# di2c.net
KiCad netlist of a schematic drawn in Altium Designer
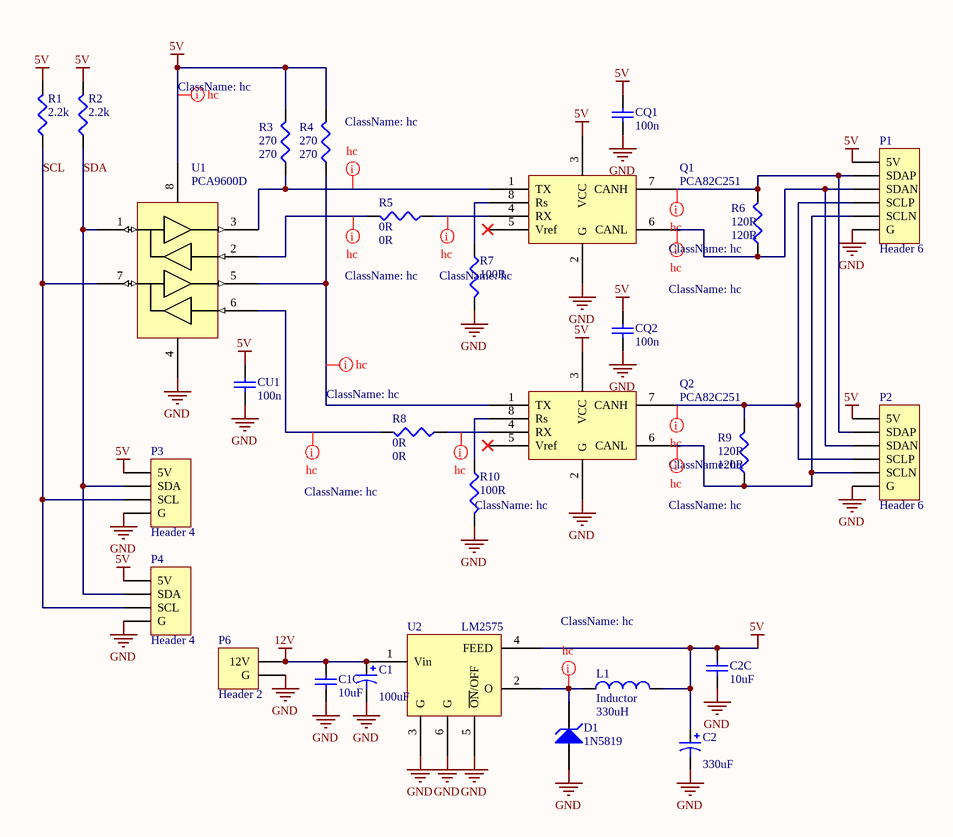
[diagram p0: di2c.SchDoc]

(export (version "E")
  (design (tool "Eeschema 10.0.6"))
  (components
    (comp (ref "C1")
      (value "100uF")
      (footprint "C7343")
      (description "Polarized Capacitor (Radial)")
      (fields (field (name "Comment") "Cap Pol1") (field (name "PUBLISHER") "Altium Limited"))
      (libsource (lib "Miscellaneous Devices") (part "Cap Pol1"))
    )
    (comp (ref "C1C")
      (value "10uF")
      (footprint "C1812")
      (description "Capacitor (Semiconductor SIM Model)")
      (fields (field (name "Comment") "Cap Semi") (field (name "PUBLISHER") "Altium Limited"))
      (libsource (lib "Miscellaneous Devices") (part "Cap Semi"))
    )
    (comp (ref "C2")
      (value "330uF")
      (footprint "C7343")
      (description "Polarized Capacitor (Radial)")
      (fields (field (name "Comment") "Cap Pol1") (field (name "PUBLISHER") "Altium Limited"))
      (libsource (lib "Miscellaneous Devices") (part "Cap Pol1"))
    )
    (comp (ref "C2C")
      (value "10uF")
      (footprint "C1812")
      (description "Capacitor (Semiconductor SIM Model)")
      (fields (field (name "Comment") "Cap Semi") (field (name "PUBLISHER") "Altium Limited"))
      (libsource (lib "Miscellaneous Devices") (part "Cap Semi"))
    )
    (comp (ref "CQ1")
      (value "100n")
      (footprint "C1206")
      (description "Capacitor (Semiconductor SIM Model)")
      (fields (field (name "Comment") "Cap Semi") (field (name "PUBLISHER") "Altium Limited"))
      (libsource (lib "Miscellaneous Devices") (part "Cap Semi"))
    )
    (comp (ref "CQ2")
      (value "100n")
      (footprint "C1206")
      (description "Capacitor (Semiconductor SIM Model)")
      (fields (field (name "Comment") "Cap Semi") (field (name "PUBLISHER") "Altium Limited"))
      (libsource (lib "Miscellaneous Devices") (part "Cap Semi"))
    )
    (comp (ref "CU1")
      (value "100n")
      (footprint "C1206")
      (description "Capacitor (Semiconductor SIM Model)")
      (fields (field (name "Comment") "Cap Semi") (field (name "PUBLISHER") "Altium Limited"))
      (libsource (lib "Miscellaneous Devices") (part "Cap Semi"))
    )
    (comp (ref "D1")
      (value "1N5819")
      (footprint "DO214AC")
      (description "Zener Diode")
      (fields (field (name "PUBLISHER") "Altium Limited"))
      (libsource (lib "Miscellaneous Devices") (part "D Zener"))
    )
    (comp (ref "L1")
      (value "Inductor")
      (footprint "CD74R")
      (fields (field (name "ALTIUM_VALUE") "330uH") (field (name "PUBLISHER") "Altium Limited"))
      (libsource (lib "Miscellaneous Devices") (part "Inductor"))
    )
    (comp (ref "P1")
      (value "Header 6")
      (footprint "HDR1X6")
      (description "Header, 6-Pin")
      (fields (field (name "PUBLISHER") "Altium Limited"))
      (libsource (lib "Miscellaneous Connectors") (part "Header 6"))
    )
    (comp (ref "P2")
      (value "Header 6")
      (footprint "HDR1X6")
      (description "Header, 6-Pin")
      (fields (field (name "PUBLISHER") "Altium Limited"))
      (libsource (lib "Miscellaneous Connectors") (part "Header 6"))
    )
    (comp (ref "P3")
      (value "Header 4")
      (footprint "HDR1X4")
      (description "Header, 4-Pin")
      (fields (field (name "PUBLISHER") "Altium Limited"))
      (libsource (lib "Miscellaneous Connectors") (part "Header 4"))
    )
    (comp (ref "P4")
      (value "Header 4")
      (footprint "HDR1X4")
      (description "Header, 4-Pin")
      (fields (field (name "PUBLISHER") "Altium Limited"))
      (libsource (lib "Miscellaneous Connectors") (part "Header 4"))
    )
    (comp (ref "P6")
      (value "Header 2")
      (footprint "HDR1X2")
      (description "Header, 2-Pin")
      (fields (field (name "PUBLISHER") "Altium Limited"))
      (libsource (lib "Miscellaneous Connectors") (part "Header 2"))
    )
    (comp (ref "Q1") (value "PCA82C251") (footprint "SOIC150-8_M") (libsource (lib "PCA") (part "PCA82C251")))
    (comp (ref "Q2") (value "PCA82C251") (footprint "SOIC150-8_M") (libsource (lib "PCA") (part "PCA82C251")))
    (comp (ref "R1")
      (value "2.2k")
      (footprint "J1-0603")
      (description "Resistor")
      (fields (field (name "PUBLISHER") "Altium Limited"))
      (libsource (lib "Miscellaneous Devices") (part "Res3"))
    )
    (comp (ref "R2")
      (value "2.2k")
      (footprint "J1-0603")
      (description "Resistor")
      (fields (field (name "PUBLISHER") "Altium Limited"))
      (libsource (lib "Miscellaneous Devices") (part "Res3"))
    )
    (comp (ref "R3")
      (value "270")
      (footprint "R1206")
      (description "Resistor")
      (fields (field (name "ALTIUM_VALUE") "270") (field (name "PUBLISHER") "Altium Limited"))
      (libsource (lib "Miscellaneous Devices") (part "Res3"))
    )
    (comp (ref "R4")
      (value "270")
      (footprint "R1206")
      (description "Resistor")
      (fields (field (name "ALTIUM_VALUE") "270") (field (name "PUBLISHER") "Altium Limited"))
      (libsource (lib "Miscellaneous Devices") (part "Res3"))
    )
    (comp (ref "R5")
      (value "0R")
      (footprint "R1206")
      (description "Resistor")
      (fields (field (name "ALTIUM_VALUE") "0R") (field (name "PUBLISHER") "Altium Limited"))
      (libsource (lib "Miscellaneous Devices") (part "Res3"))
    )
    (comp (ref "R6")
      (value "120R")
      (footprint "R1206")
      (description "Resistor")
      (fields (field (name "ALTIUM_VALUE") "120R") (field (name "PUBLISHER") "Altium Limited"))
      (libsource (lib "Miscellaneous Devices") (part "Res3"))
    )
    (comp (ref "R7")
      (value "100R")
      (footprint "J1-0603")
      (description "Resistor")
      (fields (field (name "PUBLISHER") "Altium Limited"))
      (libsource (lib "Miscellaneous Devices") (part "Res3"))
    )
    (comp (ref "R8")
      (value "0R")
      (footprint "R1206")
      (description "Resistor")
      (fields (field (name "ALTIUM_VALUE") "0R") (field (name "PUBLISHER") "Altium Limited"))
      (libsource (lib "Miscellaneous Devices") (part "Res3"))
    )
    (comp (ref "R9")
      (value "120R")
      (footprint "R1206")
      (description "Resistor")
      (fields (field (name "ALTIUM_VALUE") "120R") (field (name "PUBLISHER") "Altium Limited"))
      (libsource (lib "Miscellaneous Devices") (part "Res3"))
    )
    (comp (ref "R10")
      (value "100R")
      (footprint "J1-0603")
      (description "Resistor")
      (fields (field (name "PUBLISHER") "Altium Limited"))
      (libsource (lib "Miscellaneous Devices") (part "Res3"))
    )
    (comp (ref "U1") (value "PCA9600D") (footprint "SOIC150-8_M") (libsource (lib "misc") (part "P82B96")))
    (comp (ref "U2") (value "LM2575") (footprint "KTT") (libsource (lib "PCA") (part "LM2575")))
  )
  (nets
    (net (code "1") (name "/SCL") (class "Default")
      (node (ref "P3") (pin "2") (pinfunction "SCL_2") (pintype "passive"))
      (node (ref "P4") (pin "2") (pinfunction "SCL_2") (pintype "passive"))
      (node (ref "R1") (pin "1") (pinfunction "1_1") (pintype "passive"))
      (node (ref "U1") (pin "7") (pinfunction "7_7") (pintype "bidirectional"))
    )
    (net (code "2") (name "/SDA") (class "Default")
      (node (ref "P3") (pin "3") (pinfunction "SDA_3") (pintype "passive"))
      (node (ref "P4") (pin "3") (pinfunction "SDA_3") (pintype "passive"))
      (node (ref "R2") (pin "1") (pinfunction "1_1") (pintype "passive"))
      (node (ref "U1") (pin "1") (pinfunction "1_1") (pintype "bidirectional"))
    )
    (net (code "3") (name "5V") (class "Default")
      (node (ref "C2") (pin "1") (pinfunction "1_1") (pintype "passive"))
      (node (ref "C2C") (pin "2") (pinfunction "2_2") (pintype "passive"))
      (node (ref "CQ1") (pin "2") (pinfunction "2_2") (pintype "passive"))
      (node (ref "CQ2") (pin "2") (pinfunction "2_2") (pintype "passive"))
      (node (ref "CU1") (pin "2") (pinfunction "2_2") (pintype "passive"))
      (node (ref "L1") (pin "2") (pinfunction "2_2") (pintype "passive"))
      (node (ref "P1") (pin "6") (pinfunction "5V_6") (pintype "passive"))
      (node (ref "P2") (pin "6") (pinfunction "5V_6") (pintype "passive"))
      (node (ref "P3") (pin "4") (pinfunction "5V_4") (pintype "passive"))
      (node (ref "P4") (pin "4") (pinfunction "5V_4") (pintype "passive"))
      (node (ref "Q1") (pin "3") (pinfunction "VCC_3") (pintype "passive"))
      (node (ref "Q2") (pin "3") (pinfunction "VCC_3") (pintype "passive"))
      (node (ref "R1") (pin "2") (pinfunction "2_2") (pintype "passive"))
      (node (ref "R2") (pin "2") (pinfunction "2_2") (pintype "passive"))
      (node (ref "R3") (pin "2") (pinfunction "2_2") (pintype "passive"))
      (node (ref "R4") (pin "2") (pinfunction "2_2") (pintype "passive"))
      (node (ref "U1") (pin "8") (pinfunction "8_8") (pintype "passive"))
      (node (ref "U2") (pin "4") (pinfunction "FEED_4") (pintype "passive"))
    )
    (net (code "4") (name "12V") (class "Default")
      (node (ref "C1") (pin "1") (pinfunction "1_1") (pintype "passive"))
      (node (ref "C1C") (pin "2") (pinfunction "2_2") (pintype "passive"))
      (node (ref "P6") (pin "2") (pinfunction "12V_2") (pintype "passive"))
      (node (ref "U2") (pin "1") (pinfunction "Vin_1") (pintype "passive"))
    )
    (net (code "5") (name "GND") (class "Default")
      (node (ref "C1") (pin "2") (pinfunction "2_2") (pintype "passive"))
      (node (ref "C1C") (pin "1") (pinfunction "1_1") (pintype "passive"))
      (node (ref "C2") (pin "2") (pinfunction "2_2") (pintype "passive"))
      (node (ref "C2C") (pin "1") (pinfunction "1_1") (pintype "passive"))
      (node (ref "CQ1") (pin "1") (pinfunction "1_1") (pintype "passive"))
      (node (ref "CQ2") (pin "1") (pinfunction "1_1") (pintype "passive"))
      (node (ref "CU1") (pin "1") (pinfunction "1_1") (pintype "passive"))
      (node (ref "D1") (pin "2") (pinfunction "A_2") (pintype "passive"))
      (node (ref "P1") (pin "1") (pinfunction "G_1") (pintype "passive"))
      (node (ref "P2") (pin "1") (pinfunction "G_1") (pintype "passive"))
      (node (ref "P3") (pin "1") (pinfunction "G_1") (pintype "passive"))
      (node (ref "P4") (pin "1") (pinfunction "G_1") (pintype "passive"))
      (node (ref "P6") (pin "1") (pinfunction "G_1") (pintype "passive"))
      (node (ref "Q1") (pin "2") (pinfunction "G_2") (pintype "passive"))
      (node (ref "Q2") (pin "2") (pinfunction "G_2") (pintype "passive"))
      (node (ref "R10") (pin "2") (pinfunction "2_2") (pintype "passive"))
      (node (ref "R7") (pin "2") (pinfunction "2_2") (pintype "passive"))
      (node (ref "U1") (pin "4") (pinfunction "4_4") (pintype "passive"))
      (node (ref "U2") (pin "3") (pinfunction "G_3") (pintype "passive"))
      (node (ref "U2") (pin "5") (pinfunction "~{ON}/OFF_5") (pintype "passive"))
      (node (ref "U2") (pin "6") (pinfunction "G_6") (pintype "passive"))
    )
    (net (code "6") (name "Net-(D1-K)") (class "Default")
      (node (ref "D1") (pin "1") (pinfunction "K_1") (pintype "passive"))
      (node (ref "L1") (pin "1") (pinfunction "1_1") (pintype "passive"))
      (node (ref "U2") (pin "2") (pinfunction "O_2") (pintype "passive"))
    )
    (net (code "7") (name "Net-(P1-SCLN)") (class "Default")
      (node (ref "P1") (pin "2") (pinfunction "SCLN_2") (pintype "passive"))
      (node (ref "P2") (pin "2") (pinfunction "SCLN_2") (pintype "passive"))
      (node (ref "Q2") (pin "6") (pinfunction "CANL_6") (pintype "passive"))
      (node (ref "R9") (pin "1") (pinfunction "1_1") (pintype "passive"))
    )
    (net (code "8") (name "Net-(P1-SCLP)") (class "Default")
      (node (ref "P1") (pin "3") (pinfunction "SCLP_3") (pintype "passive"))
      (node (ref "P2") (pin "3") (pinfunction "SCLP_3") (pintype "passive"))
      (node (ref "Q2") (pin "7") (pinfunction "CANH_7") (pintype "passive"))
      (node (ref "R9") (pin "2") (pinfunction "2_2") (pintype "passive"))
    )
    (net (code "9") (name "Net-(P1-SDAN)") (class "Default")
      (node (ref "P1") (pin "4") (pinfunction "SDAN_4") (pintype "passive"))
      (node (ref "P2") (pin "4") (pinfunction "SDAN_4") (pintype "passive"))
      (node (ref "Q1") (pin "6") (pinfunction "CANL_6") (pintype "passive"))
      (node (ref "R6") (pin "1") (pinfunction "1_1") (pintype "passive"))
    )
    (net (code "10") (name "Net-(P1-SDAP)") (class "Default")
      (node (ref "P1") (pin "5") (pinfunction "SDAP_5") (pintype "passive"))
      (node (ref "P2") (pin "5") (pinfunction "SDAP_5") (pintype "passive"))
      (node (ref "Q1") (pin "7") (pinfunction "CANH_7") (pintype "passive"))
      (node (ref "R6") (pin "2") (pinfunction "2_2") (pintype "passive"))
    )
    (net (code "11") (name "Net-(Q1-RX)") (class "Default")
      (node (ref "Q1") (pin "4") (pinfunction "RX_4") (pintype "passive"))
      (node (ref "R5") (pin "1") (pinfunction "1_1") (pintype "passive"))
    )
    (net (code "12") (name "Net-(Q1-Rs)") (class "Default")
      (node (ref "Q1") (pin "8") (pinfunction "Rs_8") (pintype "passive"))
      (node (ref "R7") (pin "1") (pinfunction "1_1") (pintype "passive"))
    )
    (net (code "13") (name "Net-(Q1-TX)") (class "Default")
      (node (ref "Q1") (pin "1") (pinfunction "TX_1") (pintype "passive"))
      (node (ref "R3") (pin "1") (pinfunction "1_1") (pintype "passive"))
      (node (ref "U1") (pin "3") (pinfunction "3_3") (pintype "output"))
    )
    (net (code "14") (name "Net-(Q2-RX)") (class "Default")
      (node (ref "Q2") (pin "4") (pinfunction "RX_4") (pintype "passive"))
      (node (ref "R8") (pin "1") (pinfunction "1_1") (pintype "passive"))
    )
    (net (code "15") (name "Net-(Q2-Rs)") (class "Default")
      (node (ref "Q2") (pin "8") (pinfunction "Rs_8") (pintype "passive"))
      (node (ref "R10") (pin "1") (pinfunction "1_1") (pintype "passive"))
    )
    (net (code "16") (name "Net-(Q2-TX)") (class "Default")
      (node (ref "Q2") (pin "1") (pinfunction "TX_1") (pintype "passive"))
      (node (ref "R4") (pin "1") (pinfunction "1_1") (pintype "passive"))
      (node (ref "U1") (pin "5") (pinfunction "5_5") (pintype "output"))
    )
    (net (code "17") (name "Net-(R5-Pad2)") (class "Default")
      (node (ref "R5") (pin "2") (pinfunction "2_2") (pintype "passive"))
      (node (ref "U1") (pin "2") (pinfunction "2_2") (pintype "input"))
    )
    (net (code "18") (name "Net-(R8-Pad2)") (class "Default")
      (node (ref "R8") (pin "2") (pinfunction "2_2") (pintype "passive"))
      (node (ref "U1") (pin "6") (pinfunction "6_6") (pintype "input"))
    )
    (net (code "19") (name "unconnected-(Q1-Vref-Pad5)") (class "Default")
      (node (ref "Q1") (pin "5") (pinfunction "Vref_5") (pintype "passive+no_connect"))
    )
    (net (code "20") (name "unconnected-(Q2-Vref-Pad5)") (class "Default")
      (node (ref "Q2") (pin "5") (pinfunction "Vref_5") (pintype "passive+no_connect"))
    )
  )
)
